# Infrared_reception.net
KiCad netlist of a schematic drawn in Altium Designer
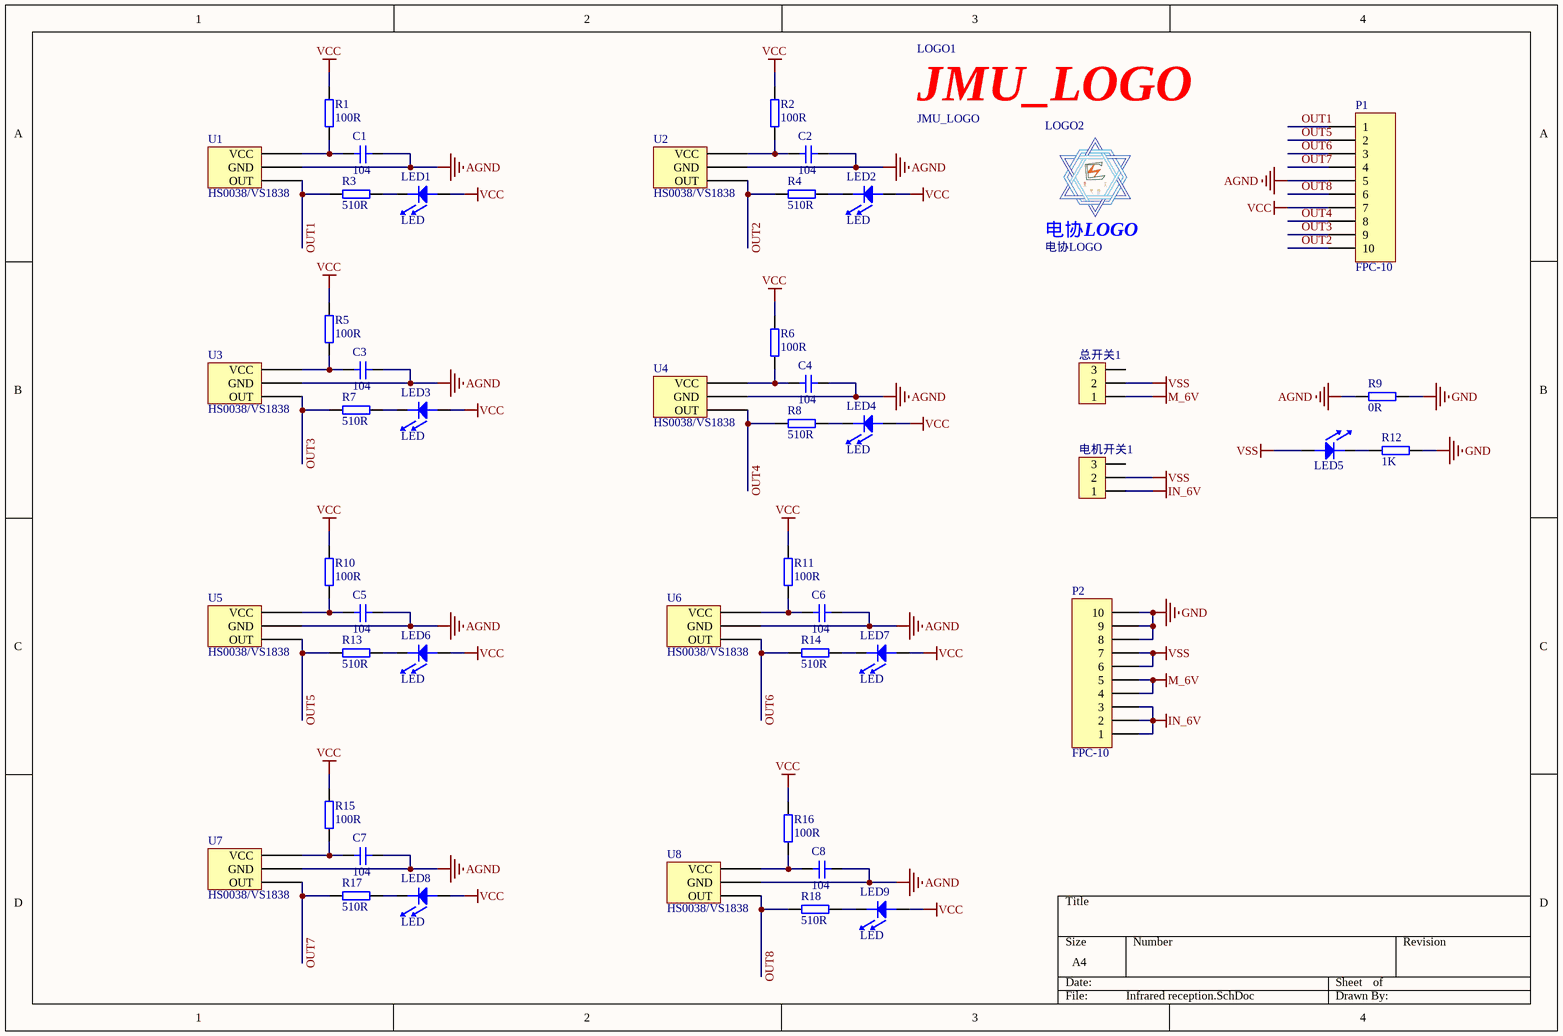
[diagram p0: Infrared reception.SchDoc]

(export (version "E")
  (design (tool "Eeschema 10.0.6"))
  (components
    (comp (ref "C1")
      (value "104")
      (footprint "0805C")
      (description "无极贴片电容")
      (libsource (lib "Integrated_Library") (part "Cap1"))
    )
    (comp (ref "C2")
      (value "104")
      (footprint "0805C")
      (description "无极贴片电容")
      (libsource (lib "Integrated_Library") (part "Cap1"))
    )
    (comp (ref "C3")
      (value "104")
      (footprint "0805C")
      (description "无极贴片电容")
      (libsource (lib "Integrated_Library") (part "Cap1"))
    )
    (comp (ref "C4")
      (value "104")
      (footprint "0805C")
      (description "无极贴片电容")
      (libsource (lib "Integrated_Library") (part "Cap1"))
    )
    (comp (ref "C5")
      (value "104")
      (footprint "0805C")
      (description "无极贴片电容")
      (libsource (lib "Integrated_Library") (part "Cap1"))
    )
    (comp (ref "C6")
      (value "104")
      (footprint "0805C")
      (description "无极贴片电容")
      (libsource (lib "Integrated_Library") (part "Cap1"))
    )
    (comp (ref "C7")
      (value "104")
      (footprint "0805C")
      (description "无极贴片电容")
      (libsource (lib "Integrated_Library") (part "Cap1"))
    )
    (comp (ref "C8")
      (value "104")
      (footprint "0805C")
      (description "无极贴片电容")
      (libsource (lib "Integrated_Library") (part "Cap1"))
    )
    (comp (ref "LED1")
      (value "LED")
      (footprint "0805LED")
      (description "发光二极管")
      (libsource (lib "Integrated_Library") (part "LED"))
    )
    (comp (ref "LED2")
      (value "LED")
      (footprint "0805LED")
      (description "发光二极管")
      (libsource (lib "Integrated_Library") (part "LED"))
    )
    (comp (ref "LED3")
      (value "LED")
      (footprint "0805LED")
      (description "发光二极管")
      (libsource (lib "Integrated_Library") (part "LED"))
    )
    (comp (ref "LED4")
      (value "LED")
      (footprint "0805LED")
      (description "发光二极管")
      (libsource (lib "Integrated_Library") (part "LED"))
    )
    (comp (ref "LED5")
      (value "LED2")
      (footprint "LED(0805)")
      (description "发光二极管")
      (libsource (lib "集大电协1.0.3") (part "LED"))
    )
    (comp (ref "LED6")
      (value "LED")
      (footprint "0805LED")
      (description "发光二极管")
      (libsource (lib "Integrated_Library") (part "LED"))
    )
    (comp (ref "LED7")
      (value "LED")
      (footprint "0805LED")
      (description "发光二极管")
      (libsource (lib "Integrated_Library") (part "LED"))
    )
    (comp (ref "LED8")
      (value "LED")
      (footprint "0805LED")
      (description "发光二极管")
      (libsource (lib "Integrated_Library") (part "LED"))
    )
    (comp (ref "LED9")
      (value "LED")
      (footprint "0805LED")
      (description "发光二极管")
      (libsource (lib "Integrated_Library") (part "LED"))
    )
    (comp (ref "LOGO1")
      (value "JMU_LOGO")
      (footprint "JMU_logo（1）")
      (description "LOGO")
      (libsource (lib "集大电协1.2") (part "JMU_LOGO"))
    )
    (comp (ref "LOGO2") (value "电协LOGO") (footprint "电协LOGO") (libsource (lib "集大电协1.2") (part "电协LOGO")))
    (comp (ref "P1")
      (value "FPC-10")
      (footprint "FPC-10")
      (description "软排线底座")
      (libsource (lib "集大电协1.1.3") (part "FPC-10"))
    )
    (comp (ref "P2")
      (value "FPC-10")
      (footprint "FPC-10")
      (description "软排线底座")
      (libsource (lib "电协封装库v1.1.4") (part "FPC-10"))
    )
    (comp (ref "R1")
      (value "100R")
      (footprint "0805R")
      (description "电阻")
      (libsource (lib "Integrated_Library") (part "Res"))
    )
    (comp (ref "R2")
      (value "100R")
      (footprint "0805R")
      (description "电阻")
      (libsource (lib "Integrated_Library") (part "Res"))
    )
    (comp (ref "R3")
      (value "510R")
      (footprint "0805R")
      (description "电阻")
      (libsource (lib "Integrated_Library") (part "Res"))
    )
    (comp (ref "R4")
      (value "510R")
      (footprint "0805R")
      (description "电阻")
      (libsource (lib "Integrated_Library") (part "Res"))
    )
    (comp (ref "R5")
      (value "100R")
      (footprint "0805R")
      (description "电阻")
      (libsource (lib "Integrated_Library") (part "Res"))
    )
    (comp (ref "R6")
      (value "100R")
      (footprint "0805R")
      (description "电阻")
      (libsource (lib "Integrated_Library") (part "Res"))
    )
    (comp (ref "R7")
      (value "510R")
      (footprint "0805R")
      (description "电阻")
      (libsource (lib "Integrated_Library") (part "Res"))
    )
    (comp (ref "R8")
      (value "510R")
      (footprint "0805R")
      (description "电阻")
      (libsource (lib "Integrated_Library") (part "Res"))
    )
    (comp (ref "R9")
      (value "0R")
      (footprint "0805R")
      (description "电阻")
      (libsource (lib "Integrated_Library") (part "Res"))
    )
    (comp (ref "R10")
      (value "100R")
      (footprint "0805R")
      (description "电阻")
      (libsource (lib "Integrated_Library") (part "Res"))
    )
    (comp (ref "R11")
      (value "100R")
      (footprint "0805R")
      (description "电阻")
      (libsource (lib "Integrated_Library") (part "Res"))
    )
    (comp (ref "R12")
      (value "1K")
      (footprint "0805R")
      (description "电阻")
      (libsource (lib "集大电协1.2") (part "Res"))
    )
    (comp (ref "R13")
      (value "510R")
      (footprint "0805R")
      (description "电阻")
      (libsource (lib "Integrated_Library") (part "Res"))
    )
    (comp (ref "R14")
      (value "510R")
      (footprint "0805R")
      (description "电阻")
      (libsource (lib "Integrated_Library") (part "Res"))
    )
    (comp (ref "R15")
      (value "100R")
      (footprint "0805R")
      (description "电阻")
      (libsource (lib "Integrated_Library") (part "Res"))
    )
    (comp (ref "R16")
      (value "100R")
      (footprint "0805R")
      (description "电阻")
      (libsource (lib "Integrated_Library") (part "Res"))
    )
    (comp (ref "R17")
      (value "510R")
      (footprint "0805R")
      (description "电阻")
      (libsource (lib "Integrated_Library") (part "Res"))
    )
    (comp (ref "R18")
      (value "510R")
      (footprint "0805R")
      (description "电阻")
      (libsource (lib "Integrated_Library") (part "Res"))
    )
    (comp (ref "U1")
      (value "HS0038/VS1838")
      (footprint "HS0038")
      (description "一体化红外接收头")
      (libsource (lib "Integrated_Library") (part "HS0038/VS1838"))
    )
    (comp (ref "U2")
      (value "HS0038/VS1838")
      (footprint "HS0038")
      (description "一体化红外接收头")
      (libsource (lib "Integrated_Library") (part "HS0038/VS1838"))
    )
    (comp (ref "U3")
      (value "HS0038/VS1838")
      (footprint "HS0038")
      (description "一体化红外接收头")
      (libsource (lib "Integrated_Library") (part "HS0038/VS1838"))
    )
    (comp (ref "U4")
      (value "HS0038/VS1838")
      (footprint "HS0038")
      (description "一体化红外接收头")
      (libsource (lib "Integrated_Library") (part "HS0038/VS1838"))
    )
    (comp (ref "U5")
      (value "HS0038/VS1838")
      (footprint "HS0038")
      (description "一体化红外接收头")
      (libsource (lib "Integrated_Library") (part "HS0038/VS1838"))
    )
    (comp (ref "U6")
      (value "HS0038/VS1838")
      (footprint "HS0038")
      (description "一体化红外接收头")
      (libsource (lib "Integrated_Library") (part "HS0038/VS1838"))
    )
    (comp (ref "U7")
      (value "HS0038/VS1838")
      (footprint "HS0038")
      (description "一体化红外接收头")
      (libsource (lib "Integrated_Library") (part "HS0038/VS1838"))
    )
    (comp (ref "U8")
      (value "HS0038/VS1838")
      (footprint "HS0038")
      (description "一体化红外接收头")
      (libsource (lib "Integrated_Library") (part "HS0038/VS1838"))
    )
    (comp (ref "总开关1")
      (value "Header 3")
      (footprint "钮子开关(小)")
      (description "排针")
      (libsource (lib "集大电协1.2") (part "Header 3"))
    )
    (comp (ref "电机开关1")
      (value "Header 3")
      (footprint "钮子开关(小)")
      (description "排针")
      (libsource (lib "集大电协1.2") (part "Header 3"))
    )
  )
  (nets
    (net (code "1") (name "/OUT1") (class "Default")
      (node (ref "P1") (pin "1") (pinfunction "1_1") (pintype "passive"))
      (node (ref "R3") (pin "1") (pinfunction "1_1") (pintype "passive"))
      (node (ref "U1") (pin "1") (pinfunction "OUT_1") (pintype "passive"))
    )
    (net (code "2") (name "/OUT2") (class "Default")
      (node (ref "P1") (pin "10") (pinfunction "10_10") (pintype "passive"))
      (node (ref "R4") (pin "1") (pinfunction "1_1") (pintype "passive"))
      (node (ref "U2") (pin "1") (pinfunction "OUT_1") (pintype "passive"))
    )
    (net (code "3") (name "/OUT3") (class "Default")
      (node (ref "P1") (pin "9") (pinfunction "9_9") (pintype "passive"))
      (node (ref "R7") (pin "1") (pinfunction "1_1") (pintype "passive"))
      (node (ref "U3") (pin "1") (pinfunction "OUT_1") (pintype "passive"))
    )
    (net (code "4") (name "/OUT4") (class "Default")
      (node (ref "P1") (pin "8") (pinfunction "8_8") (pintype "passive"))
      (node (ref "R8") (pin "1") (pinfunction "1_1") (pintype "passive"))
      (node (ref "U4") (pin "1") (pinfunction "OUT_1") (pintype "passive"))
    )
    (net (code "5") (name "/OUT5") (class "Default")
      (node (ref "P1") (pin "2") (pinfunction "2_2") (pintype "passive"))
      (node (ref "R13") (pin "1") (pinfunction "1_1") (pintype "passive"))
      (node (ref "U5") (pin "1") (pinfunction "OUT_1") (pintype "passive"))
    )
    (net (code "6") (name "/OUT6") (class "Default")
      (node (ref "P1") (pin "3") (pinfunction "3_3") (pintype "passive"))
      (node (ref "R14") (pin "1") (pinfunction "1_1") (pintype "passive"))
      (node (ref "U6") (pin "1") (pinfunction "OUT_1") (pintype "passive"))
    )
    (net (code "7") (name "/OUT7") (class "Default")
      (node (ref "P1") (pin "4") (pinfunction "4_4") (pintype "passive"))
      (node (ref "R17") (pin "1") (pinfunction "1_1") (pintype "passive"))
      (node (ref "U7") (pin "1") (pinfunction "OUT_1") (pintype "passive"))
    )
    (net (code "8") (name "/OUT8") (class "Default")
      (node (ref "P1") (pin "6") (pinfunction "6_6") (pintype "passive"))
      (node (ref "R18") (pin "1") (pinfunction "1_1") (pintype "passive"))
      (node (ref "U8") (pin "1") (pinfunction "OUT_1") (pintype "passive"))
    )
    (net (code "9") (name "AGND") (class "Default")
      (node (ref "C1") (pin "2") (pinfunction "2_2") (pintype "passive"))
      (node (ref "C2") (pin "2") (pinfunction "2_2") (pintype "passive"))
      (node (ref "C3") (pin "2") (pinfunction "2_2") (pintype "passive"))
      (node (ref "C4") (pin "2") (pinfunction "2_2") (pintype "passive"))
      (node (ref "C5") (pin "2") (pinfunction "2_2") (pintype "passive"))
      (node (ref "C6") (pin "2") (pinfunction "2_2") (pintype "passive"))
      (node (ref "C7") (pin "2") (pinfunction "2_2") (pintype "passive"))
      (node (ref "C8") (pin "2") (pinfunction "2_2") (pintype "passive"))
      (node (ref "P1") (pin "5") (pinfunction "5_5") (pintype "passive"))
      (node (ref "R9") (pin "1") (pinfunction "1_1") (pintype "passive"))
      (node (ref "U1") (pin "2") (pinfunction "GND_2") (pintype "passive"))
      (node (ref "U2") (pin "2") (pinfunction "GND_2") (pintype "passive"))
      (node (ref "U3") (pin "2") (pinfunction "GND_2") (pintype "passive"))
      (node (ref "U4") (pin "2") (pinfunction "GND_2") (pintype "passive"))
      (node (ref "U5") (pin "2") (pinfunction "GND_2") (pintype "passive"))
      (node (ref "U6") (pin "2") (pinfunction "GND_2") (pintype "passive"))
      (node (ref "U7") (pin "2") (pinfunction "GND_2") (pintype "passive"))
      (node (ref "U8") (pin "2") (pinfunction "GND_2") (pintype "passive"))
    )
    (net (code "10") (name "GND") (class "Default")
      (node (ref "P2") (pin "10") (pinfunction "10_10") (pintype "passive"))
      (node (ref "P2") (pin "8") (pinfunction "8_8") (pintype "passive"))
      (node (ref "P2") (pin "9") (pinfunction "9_9") (pintype "passive"))
      (node (ref "R12") (pin "1") (pinfunction "1_1") (pintype "passive"))
      (node (ref "R9") (pin "2") (pinfunction "2_2") (pintype "passive"))
    )
    (net (code "11") (name "IN_6V") (class "Default")
      (node (ref "P2") (pin "1") (pinfunction "1_1") (pintype "passive"))
      (node (ref "P2") (pin "2") (pinfunction "2_2") (pintype "passive"))
      (node (ref "P2") (pin "3") (pinfunction "3_3") (pintype "passive"))
      (node (ref "电机开关1") (pin "1") (pinfunction "1_1") (pintype "passive"))
    )
    (net (code "12") (name "M_6V") (class "Default")
      (node (ref "P2") (pin "4") (pinfunction "4_4") (pintype "passive"))
      (node (ref "P2") (pin "5") (pinfunction "5_5") (pintype "passive"))
      (node (ref "总开关1") (pin "1") (pinfunction "1_1") (pintype "passive"))
    )
    (net (code "13") (name "Net-(LED1-Pad2)") (class "Default")
      (node (ref "LED1") (pin "2") (pinfunction "2_2") (pintype "passive"))
      (node (ref "R3") (pin "2") (pinfunction "2_2") (pintype "passive"))
    )
    (net (code "14") (name "Net-(LED2-Pad2)") (class "Default")
      (node (ref "LED2") (pin "2") (pinfunction "2_2") (pintype "passive"))
      (node (ref "R4") (pin "2") (pinfunction "2_2") (pintype "passive"))
    )
    (net (code "15") (name "Net-(LED3-Pad2)") (class "Default")
      (node (ref "LED3") (pin "2") (pinfunction "2_2") (pintype "passive"))
      (node (ref "R7") (pin "2") (pinfunction "2_2") (pintype "passive"))
    )
    (net (code "16") (name "Net-(LED4-Pad2)") (class "Default")
      (node (ref "LED4") (pin "2") (pinfunction "2_2") (pintype "passive"))
      (node (ref "R8") (pin "2") (pinfunction "2_2") (pintype "passive"))
    )
    (net (code "17") (name "Net-(LED5-Pad2)") (class "Default")
      (node (ref "LED5") (pin "2") (pinfunction "2_2") (pintype "passive"))
      (node (ref "R12") (pin "2") (pinfunction "2_2") (pintype "passive"))
    )
    (net (code "18") (name "Net-(LED6-Pad2)") (class "Default")
      (node (ref "LED6") (pin "2") (pinfunction "2_2") (pintype "passive"))
      (node (ref "R13") (pin "2") (pinfunction "2_2") (pintype "passive"))
    )
    (net (code "19") (name "Net-(LED7-Pad2)") (class "Default")
      (node (ref "LED7") (pin "2") (pinfunction "2_2") (pintype "passive"))
      (node (ref "R14") (pin "2") (pinfunction "2_2") (pintype "passive"))
    )
    (net (code "20") (name "Net-(LED8-Pad2)") (class "Default")
      (node (ref "LED8") (pin "2") (pinfunction "2_2") (pintype "passive"))
      (node (ref "R17") (pin "2") (pinfunction "2_2") (pintype "passive"))
    )
    (net (code "21") (name "Net-(LED9-Pad2)") (class "Default")
      (node (ref "LED9") (pin "2") (pinfunction "2_2") (pintype "passive"))
      (node (ref "R18") (pin "2") (pinfunction "2_2") (pintype "passive"))
    )
    (net (code "22") (name "Net-(U1-VCC)") (class "Default")
      (node (ref "C1") (pin "1") (pinfunction "1_1") (pintype "passive"))
      (node (ref "R1") (pin "1") (pinfunction "1_1") (pintype "passive"))
      (node (ref "U1") (pin "3") (pinfunction "VCC_3") (pintype "passive"))
    )
    (net (code "23") (name "Net-(U2-VCC)") (class "Default")
      (node (ref "C2") (pin "1") (pinfunction "1_1") (pintype "passive"))
      (node (ref "R2") (pin "1") (pinfunction "1_1") (pintype "passive"))
      (node (ref "U2") (pin "3") (pinfunction "VCC_3") (pintype "passive"))
    )
    (net (code "24") (name "Net-(U3-VCC)") (class "Default")
      (node (ref "C3") (pin "1") (pinfunction "1_1") (pintype "passive"))
      (node (ref "R5") (pin "1") (pinfunction "1_1") (pintype "passive"))
      (node (ref "U3") (pin "3") (pinfunction "VCC_3") (pintype "passive"))
    )
    (net (code "25") (name "Net-(U4-VCC)") (class "Default")
      (node (ref "C4") (pin "1") (pinfunction "1_1") (pintype "passive"))
      (node (ref "R6") (pin "1") (pinfunction "1_1") (pintype "passive"))
      (node (ref "U4") (pin "3") (pinfunction "VCC_3") (pintype "passive"))
    )
    (net (code "26") (name "Net-(U5-VCC)") (class "Default")
      (node (ref "C5") (pin "1") (pinfunction "1_1") (pintype "passive"))
      (node (ref "R10") (pin "1") (pinfunction "1_1") (pintype "passive"))
      (node (ref "U5") (pin "3") (pinfunction "VCC_3") (pintype "passive"))
    )
    (net (code "27") (name "Net-(U6-VCC)") (class "Default")
      (node (ref "C6") (pin "1") (pinfunction "1_1") (pintype "passive"))
      (node (ref "R11") (pin "1") (pinfunction "1_1") (pintype "passive"))
      (node (ref "U6") (pin "3") (pinfunction "VCC_3") (pintype "passive"))
    )
    (net (code "28") (name "Net-(U7-VCC)") (class "Default")
      (node (ref "C7") (pin "1") (pinfunction "1_1") (pintype "passive"))
      (node (ref "R15") (pin "1") (pinfunction "1_1") (pintype "passive"))
      (node (ref "U7") (pin "3") (pinfunction "VCC_3") (pintype "passive"))
    )
    (net (code "29") (name "Net-(U8-VCC)") (class "Default")
      (node (ref "C8") (pin "1") (pinfunction "1_1") (pintype "passive"))
      (node (ref "R16") (pin "1") (pinfunction "1_1") (pintype "passive"))
      (node (ref "U8") (pin "3") (pinfunction "VCC_3") (pintype "passive"))
    )
    (net (code "30") (name "VCC") (class "Default")
      (node (ref "LED1") (pin "1") (pintype "passive"))
      (node (ref "LED2") (pin "1") (pintype "passive"))
      (node (ref "LED3") (pin "1") (pintype "passive"))
      (node (ref "LED4") (pin "1") (pintype "passive"))
      (node (ref "LED6") (pin "1") (pintype "passive"))
      (node (ref "LED7") (pin "1") (pintype "passive"))
      (node (ref "LED8") (pin "1") (pintype "passive"))
      (node (ref "LED9") (pin "1") (pintype "passive"))
      (node (ref "P1") (pin "7") (pinfunction "7_7") (pintype "passive"))
      (node (ref "R1") (pin "2") (pinfunction "2_2") (pintype "passive"))
      (node (ref "R10") (pin "2") (pinfunction "2_2") (pintype "passive"))
      (node (ref "R11") (pin "2") (pinfunction "2_2") (pintype "passive"))
      (node (ref "R15") (pin "2") (pinfunction "2_2") (pintype "passive"))
      (node (ref "R16") (pin "2") (pinfunction "2_2") (pintype "passive"))
      (node (ref "R2") (pin "2") (pinfunction "2_2") (pintype "passive"))
      (node (ref "R5") (pin "2") (pinfunction "2_2") (pintype "passive"))
      (node (ref "R6") (pin "2") (pinfunction "2_2") (pintype "passive"))
    )
    (net (code "31") (name "VSS") (class "Default")
      (node (ref "LED5") (pin "1") (pintype "passive"))
      (node (ref "P2") (pin "6") (pinfunction "6_6") (pintype "passive"))
      (node (ref "P2") (pin "7") (pinfunction "7_7") (pintype "passive"))
      (node (ref "总开关1") (pin "2") (pinfunction "2_2") (pintype "passive"))
      (node (ref "电机开关1") (pin "2") (pinfunction "2_2") (pintype "passive"))
    )
    (net (code "32") (name "unconnected-(总开关1-Pad3)") (class "Default")
      (node (ref "总开关1") (pin "3") (pinfunction "3_3") (pintype "passive"))
    )
    (net (code "33") (name "unconnected-(电机开关1-Pad3)") (class "Default")
      (node (ref "电机开关1") (pin "3") (pinfunction "3_3") (pintype "passive"))
    )
  )
)
